# FSE_TSAL_trigger_schematic_1.net
KiCad netlist of a schematic drawn in EAGLE
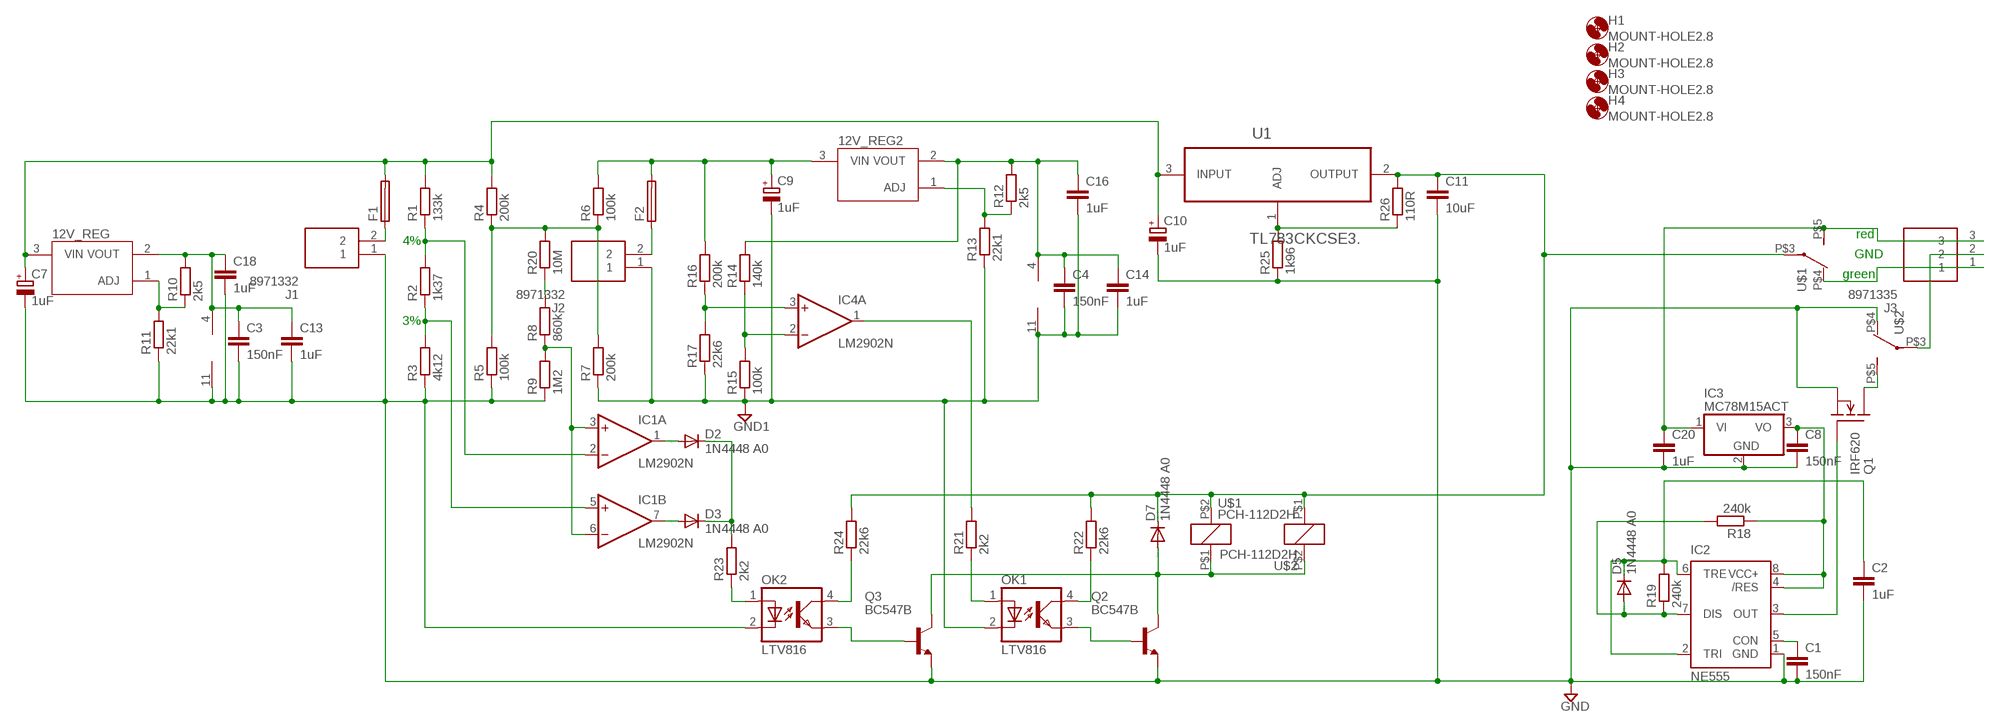
[diagram p0: schematic, sheet 1]

(export (version "E")
  (design (tool "Eeschema 10.0.6"))
  (components
    (comp (ref "12V_REG")
      (value "LR8LR8")
      (footprint "eagle-import:TO92-LINE")
      (libsource (lib "eagle-import") (part "LR8LR8"))
    )
    (comp (ref "12V_REG2")
      (value "LR8LR8")
      (footprint "eagle-import:TO92-LINE")
      (libsource (lib "eagle-import") (part "LR8LR8"))
    )
    (comp (ref "C1")
      (value "150nF")
      (footprint "eagle-import:C050-024X044")
      (libsource (lib "eagle-import") (part "C-EU050-024X044"))
    )
    (comp (ref "C2")
      (value "1uF")
      (footprint "eagle-import:C025-030X050")
      (libsource (lib "eagle-import") (part "C-EU025-030X050"))
    )
    (comp (ref "C3")
      (value "150nF")
      (footprint "eagle-import:C050-024X044")
      (libsource (lib "eagle-import") (part "C-EU050-024X044"))
    )
    (comp (ref "C4")
      (value "150nF")
      (footprint "eagle-import:C050-024X044")
      (libsource (lib "eagle-import") (part "C-EU050-024X044"))
    )
    (comp (ref "C7")
      (value "1uF")
      (footprint "eagle-import:E3,5-8")
      (libsource (lib "eagle-import") (part "CPOL-EUE3.5-8"))
    )
    (comp (ref "C8")
      (value "150nF")
      (footprint "eagle-import:C050-024X044")
      (libsource (lib "eagle-import") (part "C-EU050-024X044"))
    )
    (comp (ref "C9")
      (value "1uF")
      (footprint "eagle-import:E3,5-8")
      (libsource (lib "eagle-import") (part "CPOL-EUE3.5-8"))
    )
    (comp (ref "C10")
      (value "1uF")
      (footprint "eagle-import:E3,5-8")
      (libsource (lib "eagle-import") (part "CPOL-EUE3.5-8"))
    )
    (comp (ref "C11")
      (value "10uF")
      (footprint "eagle-import:C050-075X075")
      (libsource (lib "eagle-import") (part "C-EU050-075X075"))
    )
    (comp (ref "C13")
      (value "1uF")
      (footprint "eagle-import:C025-030X050")
      (libsource (lib "eagle-import") (part "C-EU025-030X050"))
    )
    (comp (ref "C14")
      (value "1uF")
      (footprint "eagle-import:C025-030X050")
      (libsource (lib "eagle-import") (part "C-EU025-030X050"))
    )
    (comp (ref "C16")
      (value "1uF")
      (footprint "eagle-import:C025-030X050")
      (libsource (lib "eagle-import") (part "C-EU025-030X050"))
    )
    (comp (ref "C18")
      (value "1uF")
      (footprint "eagle-import:C025-030X050")
      (libsource (lib "eagle-import") (part "C-EU025-030X050"))
    )
    (comp (ref "C20")
      (value "1uF")
      (footprint "eagle-import:C025-030X050")
      (libsource (lib "eagle-import") (part "C-EU025-030X050"))
    )
    (comp (ref "D2")
      (value "1N4448 A0")
      (footprint "eagle-import:DO35-10")
      (libsource (lib "eagle-import") (part "1N4446"))
    )
    (comp (ref "D3")
      (value "1N4448 A0")
      (footprint "eagle-import:DO35-10")
      (libsource (lib "eagle-import") (part "1N4446"))
    )
    (comp (ref "D5")
      (value "1N4448 A0")
      (footprint "eagle-import:DO35-10")
      (libsource (lib "eagle-import") (part "1N4446"))
    )
    (comp (ref "D7")
      (value "1N4448 A0")
      (footprint "eagle-import:DO35-10")
      (libsource (lib "eagle-import") (part "1N4446"))
    )
    (comp (ref "F1")
      (value "GSH15")
      (footprint "eagle-import:GSH15")
      (fields (field (name "MPN") "64900001039"))
      (libsource (lib "eagle-import") (part "GSH15"))
    )
    (comp (ref "F2")
      (value "GSH15")
      (footprint "eagle-import:GSH15")
      (fields (field (name "MPN") "64900001039"))
      (libsource (lib "eagle-import") (part "GSH15"))
    )
    (comp (ref "H1")
      (value "MOUNT-HOLE2.8")
      (footprint "eagle-import:2,8")
      (libsource (lib "eagle-import") (part "MOUNT-HOLE2.8"))
    )
    (comp (ref "H2")
      (value "MOUNT-HOLE2.8")
      (footprint "eagle-import:2,8")
      (libsource (lib "eagle-import") (part "MOUNT-HOLE2.8"))
    )
    (comp (ref "H3")
      (value "MOUNT-HOLE2.8")
      (footprint "eagle-import:2,8")
      (libsource (lib "eagle-import") (part "MOUNT-HOLE2.8"))
    )
    (comp (ref "H4")
      (value "MOUNT-HOLE2.8")
      (footprint "eagle-import:2,8")
      (libsource (lib "eagle-import") (part "MOUNT-HOLE2.8"))
    )
    (comp (ref "IC1")
      (value "LM2902N")
      (footprint "eagle-import:DIL14")
      (libsource (lib "eagle-import") (part "LM2902N"))
    )
    (comp (ref "IC2")
      (value "NE555")
      (footprint "eagle-import:DIL-08")
      (fields (field (name "MF") "Arrow Electronics") (field (name "MPN") "NE555N"))
      (libsource (lib "eagle-import") (part "NE555"))
    )
    (comp (ref "IC3")
      (value "MC78M15ACT")
      (footprint "eagle-import:TO220V")
      (libsource (lib "eagle-import") (part "MC78MT15AC"))
    )
    (comp (ref "IC4")
      (value "LM2902N")
      (footprint "eagle-import:DIL14")
      (libsource (lib "eagle-import") (part "LM2902N"))
    )
    (comp (ref "J1")
      (value "8971332")
      (footprint "eagle-import:SHDR2W90P0X350_1X2_700X700X850")
      (libsource (lib "eagle-import") (part "8971332"))
    )
    (comp (ref "J2")
      (value "8971332")
      (footprint "eagle-import:SHDR2W90P0X350_1X2_700X700X850")
      (libsource (lib "eagle-import") (part "8971332"))
    )
    (comp (ref "J3")
      (value "8971335")
      (footprint "eagle-import:SHDR3W90P0X350_1X3_1050X700X85")
      (libsource (lib "eagle-import") (part "8971335"))
    )
    (comp (ref "OK1")
      (value "LTV816")
      (footprint "eagle-import:DIL04")
      (libsource (lib "eagle-import") (part "LTV816"))
    )
    (comp (ref "OK2")
      (value "LTV816")
      (footprint "eagle-import:DIL04")
      (libsource (lib "eagle-import") (part "LTV816"))
    )
    (comp (ref "Q1")
      (value "IRF620")
      (footprint "eagle-import:TO220")
      (libsource (lib "eagle-import") (part "IRF620"))
    )
    (comp (ref "Q2")
      (value "BC547B")
      (footprint "eagle-import:TO92")
      (libsource (lib "eagle-import") (part "BC547B"))
    )
    (comp (ref "Q3")
      (value "BC547B")
      (footprint "eagle-import:TO92")
      (libsource (lib "eagle-import") (part "BC547B"))
    )
    (comp (ref "R1")
      (value "133k")
      (footprint "eagle-import:0207_10")
      (libsource (lib "eagle-import") (part "R-EU_0207/10"))
    )
    (comp (ref "R2")
      (value "1k37")
      (footprint "eagle-import:0207_10")
      (libsource (lib "eagle-import") (part "R-EU_0207/10"))
    )
    (comp (ref "R3")
      (value "4k12")
      (footprint "eagle-import:0207_10")
      (libsource (lib "eagle-import") (part "R-EU_0207/10"))
    )
    (comp (ref "R4")
      (value "200k")
      (footprint "eagle-import:0207_10")
      (libsource (lib "eagle-import") (part "R-EU_0207/10"))
    )
    (comp (ref "R5")
      (value "100k")
      (footprint "eagle-import:0207_10")
      (libsource (lib "eagle-import") (part "R-EU_0207/10"))
    )
    (comp (ref "R6")
      (value "100k")
      (footprint "eagle-import:0207_10")
      (libsource (lib "eagle-import") (part "R-EU_0207/10"))
    )
    (comp (ref "R7")
      (value "200k")
      (footprint "eagle-import:0207_10")
      (libsource (lib "eagle-import") (part "R-EU_0207/10"))
    )
    (comp (ref "R8")
      (value "860k")
      (footprint "eagle-import:0207_10")
      (libsource (lib "eagle-import") (part "R-EU_0207/10"))
    )
    (comp (ref "R9")
      (value "1M2")
      (footprint "eagle-import:0207_10")
      (libsource (lib "eagle-import") (part "R-EU_0207/10"))
    )
    (comp (ref "R10")
      (value "2k5")
      (footprint "eagle-import:0207_10")
      (libsource (lib "eagle-import") (part "R-EU_0207/10"))
    )
    (comp (ref "R11")
      (value "22k1")
      (footprint "eagle-import:0207_10")
      (libsource (lib "eagle-import") (part "R-EU_0207/10"))
    )
    (comp (ref "R12")
      (value "2k5")
      (footprint "eagle-import:0207_10")
      (libsource (lib "eagle-import") (part "R-EU_0207/10"))
    )
    (comp (ref "R13")
      (value "22k1")
      (footprint "eagle-import:0207_10")
      (libsource (lib "eagle-import") (part "R-EU_0207/10"))
    )
    (comp (ref "R14")
      (value "140k")
      (footprint "eagle-import:0207_10")
      (libsource (lib "eagle-import") (part "R-EU_0207/10"))
    )
    (comp (ref "R15")
      (value "100k")
      (footprint "eagle-import:0207_10")
      (libsource (lib "eagle-import") (part "R-EU_0207/10"))
    )
    (comp (ref "R16")
      (value "200k")
      (footprint "eagle-import:0207_10")
      (libsource (lib "eagle-import") (part "R-EU_0207/10"))
    )
    (comp (ref "R17")
      (value "22k6")
      (footprint "eagle-import:0207_10")
      (libsource (lib "eagle-import") (part "R-EU_0207/10"))
    )
    (comp (ref "R18")
      (value "240k")
      (footprint "eagle-import:0207_10")
      (libsource (lib "eagle-import") (part "R-EU_0207/10"))
    )
    (comp (ref "R19")
      (value "240k")
      (footprint "eagle-import:0207_10")
      (libsource (lib "eagle-import") (part "R-EU_0207/10"))
    )
    (comp (ref "R20")
      (value "10M")
      (footprint "eagle-import:0207_10")
      (libsource (lib "eagle-import") (part "R-EU_0207/10"))
    )
    (comp (ref "R21")
      (value "2k2")
      (footprint "eagle-import:0207_10")
      (libsource (lib "eagle-import") (part "R-EU_0207/10"))
    )
    (comp (ref "R22")
      (value "22k6")
      (footprint "eagle-import:0207_10")
      (libsource (lib "eagle-import") (part "R-EU_0207/10"))
    )
    (comp (ref "R23")
      (value "2k2")
      (footprint "eagle-import:0207_10")
      (libsource (lib "eagle-import") (part "R-EU_0207/10"))
    )
    (comp (ref "R24")
      (value "22k6")
      (footprint "eagle-import:0207_10")
      (libsource (lib "eagle-import") (part "R-EU_0207/10"))
    )
    (comp (ref "R25")
      (value "1k96")
      (footprint "eagle-import:0309_10")
      (libsource (lib "eagle-import") (part "R-EU_0309/10"))
    )
    (comp (ref "R26")
      (value "110R")
      (footprint "eagle-import:0309_10")
      (libsource (lib "eagle-import") (part "R-EU_0309/10"))
    )
    (comp (ref "U$1")
      (value "PCH-112D2H")
      (footprint "eagle-import:PCH-112D2H")
      (libsource (lib "eagle-import") (part "PCH-112D2H"))
    )
    (comp (ref "U$2")
      (value "PCH-112D2H")
      (footprint "eagle-import:PCH-112D2H")
      (libsource (lib "eagle-import") (part "PCH-112D2H"))
    )
    (comp (ref "U1")
      (value "TL783CKCSE3.")
      (footprint "eagle-import:TO254P457X1016X2222-3P")
      (libsource (lib "eagle-import") (part "TL783CKCSE3."))
    )
  )
  (nets
    (net (code "1") (name "GND") (class "Default")
      (node (ref "C1") (pin "2") (pinfunction "2_2") (pintype "passive"))
      (node (ref "C10") (pin "-") (pinfunction "-_-") (pintype "passive"))
      (node (ref "C11") (pin "2") (pinfunction "2_2") (pintype "passive"))
      (node (ref "C13") (pin "2") (pinfunction "2_2") (pintype "passive"))
      (node (ref "C18") (pin "2") (pinfunction "2_2") (pintype "passive"))
      (node (ref "C2") (pin "2") (pinfunction "2_2") (pintype "passive"))
      (node (ref "C20") (pin "2") (pinfunction "2_2") (pintype "passive"))
      (node (ref "C3") (pin "2") (pinfunction "2_2") (pintype "passive"))
      (node (ref "C7") (pin "-") (pinfunction "-_-") (pintype "passive"))
      (node (ref "C8") (pin "2") (pinfunction "2_2") (pintype "passive"))
      (node (ref "IC1") (pin "11") (pinfunction "V-_11") (pintype "power_in"))
      (node (ref "IC2") (pin "1") (pinfunction "GND_1") (pintype "power_in"))
      (node (ref "IC3") (pin "2") (pinfunction "GND_2") (pintype "passive"))
      (node (ref "J1") (pin "1") (pinfunction "1_1") (pintype "bidirectional"))
      (node (ref "OK2") (pin "2") (pinfunction "C_2") (pintype "passive"))
      (node (ref "Q1") (pin "3") (pinfunction "S_3") (pintype "passive"))
      (node (ref "Q2") (pin "1") (pinfunction "E_1") (pintype "passive"))
      (node (ref "Q3") (pin "1") (pinfunction "E_1") (pintype "passive"))
      (node (ref "R11") (pin "1") (pinfunction "1_1") (pintype "passive"))
      (node (ref "R25") (pin "1") (pinfunction "1_1") (pintype "passive"))
      (node (ref "R3") (pin "1") (pinfunction "1_1") (pintype "passive"))
      (node (ref "R5") (pin "1") (pinfunction "1_1") (pintype "passive"))
      (node (ref "R9") (pin "1") (pinfunction "1_1") (pintype "passive"))
      (node (ref "U$2") (pin "P$4") (pinfunction "O_P$4") (pintype "passive"))
    )
    (net (code "2") (name "GND1") (class "Default")
      (node (ref "C14") (pin "2") (pinfunction "2_2") (pintype "passive"))
      (node (ref "C16") (pin "2") (pinfunction "2_2") (pintype "passive"))
      (node (ref "C4") (pin "2") (pinfunction "2_2") (pintype "passive"))
      (node (ref "C9") (pin "-") (pinfunction "-_-") (pintype "passive"))
      (node (ref "IC4") (pin "11") (pinfunction "V-_11") (pintype "power_in"))
      (node (ref "J2") (pin "1") (pinfunction "1_1") (pintype "bidirectional"))
      (node (ref "OK1") (pin "2") (pinfunction "C_2") (pintype "passive"))
      (node (ref "R13") (pin "1") (pinfunction "1_1") (pintype "passive"))
      (node (ref "R15") (pin "1") (pinfunction "1_1") (pintype "passive"))
      (node (ref "R17") (pin "1") (pinfunction "1_1") (pintype "passive"))
      (node (ref "R7") (pin "1") (pinfunction "1_1") (pintype "passive"))
    )
    (net (code "3") (name "Net-(12V_REG-ADJ)") (class "Default")
      (node (ref "12V_REG") (pin "1") (pinfunction "ADJ_1") (pintype "bidirectional"))
      (node (ref "R10") (pin "1") (pinfunction "1_1") (pintype "passive"))
      (node (ref "R11") (pin "2") (pinfunction "2_2") (pintype "passive"))
    )
    (net (code "4") (name "Net-(12V_REG-VIN)") (class "Default")
      (node (ref "12V_REG") (pin "3") (pinfunction "VIN_3") (pintype "bidirectional"))
      (node (ref "C10") (pin "+") (pinfunction "+_+") (pintype "passive"))
      (node (ref "C7") (pin "+") (pinfunction "+_+") (pintype "passive"))
      (node (ref "F1") (pin "2") (pinfunction "2_2") (pintype "passive"))
      (node (ref "R1") (pin "2") (pinfunction "2_2") (pintype "passive"))
      (node (ref "R4") (pin "2") (pinfunction "2_2") (pintype "passive"))
      (node (ref "U1") (pin "3") (pinfunction "INPUT_3") (pintype "input"))
    )
    (net (code "5") (name "Net-(12V_REG-VOUT)") (class "Default")
      (node (ref "12V_REG") (pin "2") (pinfunction "VOUT_2") (pintype "bidirectional"))
      (node (ref "C13") (pin "1") (pinfunction "1_1") (pintype "passive"))
      (node (ref "C18") (pin "1") (pinfunction "1_1") (pintype "passive"))
      (node (ref "C3") (pin "1") (pinfunction "1_1") (pintype "passive"))
      (node (ref "IC1") (pin "4") (pinfunction "V+_4") (pintype "power_in"))
      (node (ref "R10") (pin "2") (pinfunction "2_2") (pintype "passive"))
    )
    (net (code "6") (name "Net-(12V_REG2-ADJ)") (class "Default")
      (node (ref "12V_REG2") (pin "1") (pinfunction "ADJ_1") (pintype "bidirectional"))
      (node (ref "R12") (pin "1") (pinfunction "1_1") (pintype "passive"))
      (node (ref "R13") (pin "2") (pinfunction "2_2") (pintype "passive"))
    )
    (net (code "7") (name "Net-(12V_REG2-VIN)") (class "Default")
      (node (ref "12V_REG2") (pin "3") (pinfunction "VIN_3") (pintype "bidirectional"))
      (node (ref "C9") (pin "+") (pinfunction "+_+") (pintype "passive"))
      (node (ref "F2") (pin "2") (pinfunction "2_2") (pintype "passive"))
      (node (ref "R16") (pin "2") (pinfunction "2_2") (pintype "passive"))
      (node (ref "R6") (pin "2") (pinfunction "2_2") (pintype "passive"))
    )
    (net (code "8") (name "Net-(12V_REG2-VOUT)") (class "Default")
      (node (ref "12V_REG2") (pin "2") (pinfunction "VOUT_2") (pintype "bidirectional"))
      (node (ref "C14") (pin "1") (pinfunction "1_1") (pintype "passive"))
      (node (ref "C16") (pin "1") (pinfunction "1_1") (pintype "passive"))
      (node (ref "C4") (pin "1") (pinfunction "1_1") (pintype "passive"))
      (node (ref "IC4") (pin "4") (pinfunction "V+_4") (pintype "power_in"))
      (node (ref "R12") (pin "2") (pinfunction "2_2") (pintype "passive"))
      (node (ref "R14") (pin "2") (pinfunction "2_2") (pintype "passive"))
    )
    (net (code "9") (name "Net-(D2-PadC)") (class "Default")
      (node (ref "D2") (pin "C") (pinfunction "C_C") (pintype "passive"))
      (node (ref "D3") (pin "C") (pinfunction "C_C") (pintype "passive"))
      (node (ref "R23") (pin "2") (pinfunction "2_2") (pintype "passive"))
    )
    (net (code "10") (name "Net-(F1-Pad1)") (class "Default")
      (node (ref "F1") (pin "1") (pinfunction "1_1") (pintype "passive"))
      (node (ref "J1") (pin "2") (pinfunction "2_2") (pintype "bidirectional"))
    )
    (net (code "11") (name "Net-(F2-Pad1)") (class "Default")
      (node (ref "F2") (pin "1") (pinfunction "1_1") (pintype "passive"))
      (node (ref "J2") (pin "2") (pinfunction "2_2") (pintype "bidirectional"))
    )
    (net (code "12") (name "Net-(IC1A-+IN)") (class "Default")
      (node (ref "IC1") (pin "3") (pinfunction "+IN_3") (pintype "input"))
      (node (ref "IC1") (pin "6") (pinfunction "-IN_6") (pintype "input"))
      (node (ref "R8") (pin "1") (pinfunction "1_1") (pintype "passive"))
      (node (ref "R9") (pin "2") (pinfunction "2_2") (pintype "passive"))
    )
    (net (code "13") (name "Net-(IC1A--IN)") (class "Default")
      (node (ref "IC1") (pin "2") (pinfunction "-IN_2") (pintype "input"))
      (node (ref "R1") (pin "1") (pinfunction "1_1") (pintype "passive"))
      (node (ref "R2") (pin "2") (pinfunction "2_2") (pintype "passive"))
    )
    (net (code "14") (name "Net-(IC1A-OUT)") (class "Default")
      (node (ref "D2") (pin "A") (pinfunction "A_A") (pintype "passive"))
      (node (ref "IC1") (pin "1") (pinfunction "OUT_1") (pintype "output"))
    )
    (net (code "15") (name "Net-(IC1B-+IN)") (class "Default")
      (node (ref "IC1") (pin "5") (pinfunction "+IN_5") (pintype "input"))
      (node (ref "R2") (pin "1") (pinfunction "1_1") (pintype "passive"))
      (node (ref "R3") (pin "2") (pinfunction "2_2") (pintype "passive"))
    )
    (net (code "16") (name "Net-(IC1B-OUT)") (class "Default")
      (node (ref "D3") (pin "A") (pinfunction "A_A") (pintype "passive"))
      (node (ref "IC1") (pin "7") (pinfunction "OUT_7") (pintype "output"))
    )
    (net (code "17") (name "Net-(IC2-CON)") (class "Default")
      (node (ref "C1") (pin "1") (pinfunction "1_1") (pintype "passive"))
      (node (ref "IC2") (pin "5") (pinfunction "CON_5") (pintype "input"))
    )
    (net (code "18") (name "Net-(IC2-DIS)") (class "Default")
      (node (ref "D5") (pin "A") (pinfunction "A_A") (pintype "passive"))
      (node (ref "IC2") (pin "7") (pinfunction "DIS_7") (pintype "input"))
      (node (ref "R18") (pin "2") (pinfunction "2_2") (pintype "passive"))
      (node (ref "R19") (pin "1") (pinfunction "1_1") (pintype "passive"))
    )
    (net (code "19") (name "Net-(IC2-OUT)") (class "Default")
      (node (ref "IC2") (pin "3") (pinfunction "OUT_3") (pintype "output"))
      (node (ref "Q1") (pin "1") (pinfunction "G_1") (pintype "passive"))
    )
    (net (code "20") (name "Net-(IC2-TRE)") (class "Default")
      (node (ref "C2") (pin "1") (pinfunction "1_1") (pintype "passive"))
      (node (ref "D5") (pin "C") (pinfunction "C_C") (pintype "passive"))
      (node (ref "IC2") (pin "2") (pinfunction "TRI_2") (pintype "input"))
      (node (ref "IC2") (pin "6") (pinfunction "TRE_6") (pintype "input"))
      (node (ref "R19") (pin "2") (pinfunction "2_2") (pintype "passive"))
    )
    (net (code "21") (name "Net-(IC2-VCC+)") (class "Default")
      (node (ref "C8") (pin "1") (pinfunction "1_1") (pintype "passive"))
      (node (ref "IC2") (pin "4") (pinfunction "/RES_4") (pintype "input"))
      (node (ref "IC2") (pin "8") (pinfunction "VCC+_8") (pintype "power_in"))
      (node (ref "IC3") (pin "3") (pinfunction "VO_3") (pintype "passive"))
      (node (ref "R18") (pin "1") (pinfunction "1_1") (pintype "passive"))
    )
    (net (code "22") (name "Net-(IC3-VI)") (class "Default")
      (node (ref "C20") (pin "1") (pinfunction "1_1") (pintype "passive"))
      (node (ref "IC3") (pin "1") (pinfunction "VI_1") (pintype "input"))
      (node (ref "J3") (pin "3") (pinfunction "3_3") (pintype "bidirectional"))
      (node (ref "U$1") (pin "P$5") (pinfunction "S_P$5") (pintype "passive"))
    )
    (net (code "23") (name "Net-(IC4A-+IN)") (class "Default")
      (node (ref "IC4") (pin "3") (pinfunction "+IN_3") (pintype "input"))
      (node (ref "R16") (pin "1") (pinfunction "1_1") (pintype "passive"))
      (node (ref "R17") (pin "2") (pinfunction "2_2") (pintype "passive"))
    )
    (net (code "24") (name "Net-(IC4A--IN)") (class "Default")
      (node (ref "IC4") (pin "2") (pinfunction "-IN_2") (pintype "input"))
      (node (ref "R14") (pin "1") (pinfunction "1_1") (pintype "passive"))
      (node (ref "R15") (pin "2") (pinfunction "2_2") (pintype "passive"))
    )
    (net (code "25") (name "Net-(IC4A-OUT)") (class "Default")
      (node (ref "IC4") (pin "1") (pinfunction "OUT_1") (pintype "output"))
      (node (ref "R21") (pin "2") (pinfunction "2_2") (pintype "passive"))
    )
    (net (code "26") (name "Net-(OK1-A)") (class "Default")
      (node (ref "OK1") (pin "1") (pinfunction "A_1") (pintype "passive"))
      (node (ref "R21") (pin "1") (pinfunction "1_1") (pintype "passive"))
    )
    (net (code "27") (name "Net-(OK1-COL)") (class "Default")
      (node (ref "OK1") (pin "4") (pinfunction "COL_4") (pintype "passive"))
      (node (ref "R22") (pin "1") (pinfunction "1_1") (pintype "passive"))
    )
    (net (code "28") (name "Net-(OK1-EMIT)") (class "Default")
      (node (ref "OK1") (pin "3") (pinfunction "EMIT_3") (pintype "passive"))
      (node (ref "Q2") (pin "2") (pinfunction "B_2") (pintype "passive"))
    )
    (net (code "29") (name "Net-(OK2-A)") (class "Default")
      (node (ref "OK2") (pin "1") (pinfunction "A_1") (pintype "passive"))
      (node (ref "R23") (pin "1") (pinfunction "1_1") (pintype "passive"))
    )
    (net (code "30") (name "Net-(OK2-COL)") (class "Default")
      (node (ref "OK2") (pin "4") (pinfunction "COL_4") (pintype "passive"))
      (node (ref "R24") (pin "1") (pinfunction "1_1") (pintype "passive"))
    )
    (net (code "31") (name "Net-(OK2-EMIT)") (class "Default")
      (node (ref "OK2") (pin "3") (pinfunction "EMIT_3") (pintype "passive"))
      (node (ref "Q3") (pin "2") (pinfunction "B_2") (pintype "passive"))
    )
    (net (code "32") (name "Net-(Q1-D)") (class "Default")
      (node (ref "Q1") (pin "2") (pinfunction "D_2") (pintype "passive"))
      (node (ref "U$2") (pin "P$5") (pinfunction "S_P$5") (pintype "passive"))
    )
    (net (code "33") (name "Net-(Q2-C)") (class "Default")
      (node (ref "D7") (pin "A") (pinfunction "A_A") (pintype "passive"))
      (node (ref "Q2") (pin "3") (pinfunction "C_3") (pintype "passive"))
      (node (ref "Q3") (pin "3") (pinfunction "C_3") (pintype "passive"))
      (node (ref "U$1") (pin "P$1") (pinfunction "2_P$1") (pintype "passive"))
      (node (ref "U$2") (pin "P$2") (pinfunction "1_P$2") (pintype "passive"))
    )
    (net (code "34") (name "Net-(R20-Pad1)") (class "Default")
      (node (ref "R20") (pin "1") (pinfunction "1_1") (pintype "passive"))
      (node (ref "R8") (pin "2") (pinfunction "2_2") (pintype "passive"))
    )
    (net (code "35") (name "Net-(R20-Pad2)") (class "Default")
      (node (ref "R20") (pin "2") (pinfunction "2_2") (pintype "passive"))
      (node (ref "R4") (pin "1") (pinfunction "1_1") (pintype "passive"))
      (node (ref "R5") (pin "2") (pinfunction "2_2") (pintype "passive"))
      (node (ref "R6") (pin "1") (pinfunction "1_1") (pintype "passive"))
      (node (ref "R7") (pin "2") (pinfunction "2_2") (pintype "passive"))
    )
    (net (code "36") (name "Net-(U$1A-1)") (class "Default")
      (node (ref "C11") (pin "1") (pinfunction "1_1") (pintype "passive"))
      (node (ref "D7") (pin "C") (pinfunction "C_C") (pintype "passive"))
      (node (ref "R22") (pin "2") (pinfunction "2_2") (pintype "passive"))
      (node (ref "R24") (pin "2") (pinfunction "2_2") (pintype "passive"))
      (node (ref "R26") (pin "2") (pinfunction "2_2") (pintype "passive"))
      (node (ref "U$1") (pin "P$2") (pinfunction "1_P$2") (pintype "passive"))
      (node (ref "U$1") (pin "P$3") (pinfunction "P_P$3") (pintype "passive"))
      (node (ref "U$2") (pin "P$1") (pinfunction "2_P$1") (pintype "passive"))
      (node (ref "U1") (pin "2") (pinfunction "OUTPUT_2") (pintype "output"))
    )
    (net (code "37") (name "Net-(U$1B-O)") (class "Default")
      (node (ref "J3") (pin "1") (pinfunction "1_1") (pintype "bidirectional"))
      (node (ref "U$1") (pin "P$4") (pinfunction "O_P$4") (pintype "passive"))
    )
    (net (code "38") (name "Net-(U$2B-P)") (class "Default")
      (node (ref "J3") (pin "2") (pinfunction "2_2") (pintype "bidirectional"))
      (node (ref "U$2") (pin "P$3") (pinfunction "P_P$3") (pintype "passive"))
    )
    (net (code "39") (name "Net-(U1-ADJ)") (class "Default")
      (node (ref "R25") (pin "2") (pinfunction "2_2") (pintype "passive"))
      (node (ref "R26") (pin "1") (pinfunction "1_1") (pintype "passive"))
      (node (ref "U1") (pin "1") (pinfunction "ADJ_1") (pintype "passive"))
    )
  )
)
